# 1_MCU.net
KiCad netlist of a schematic drawn in Altium Designer
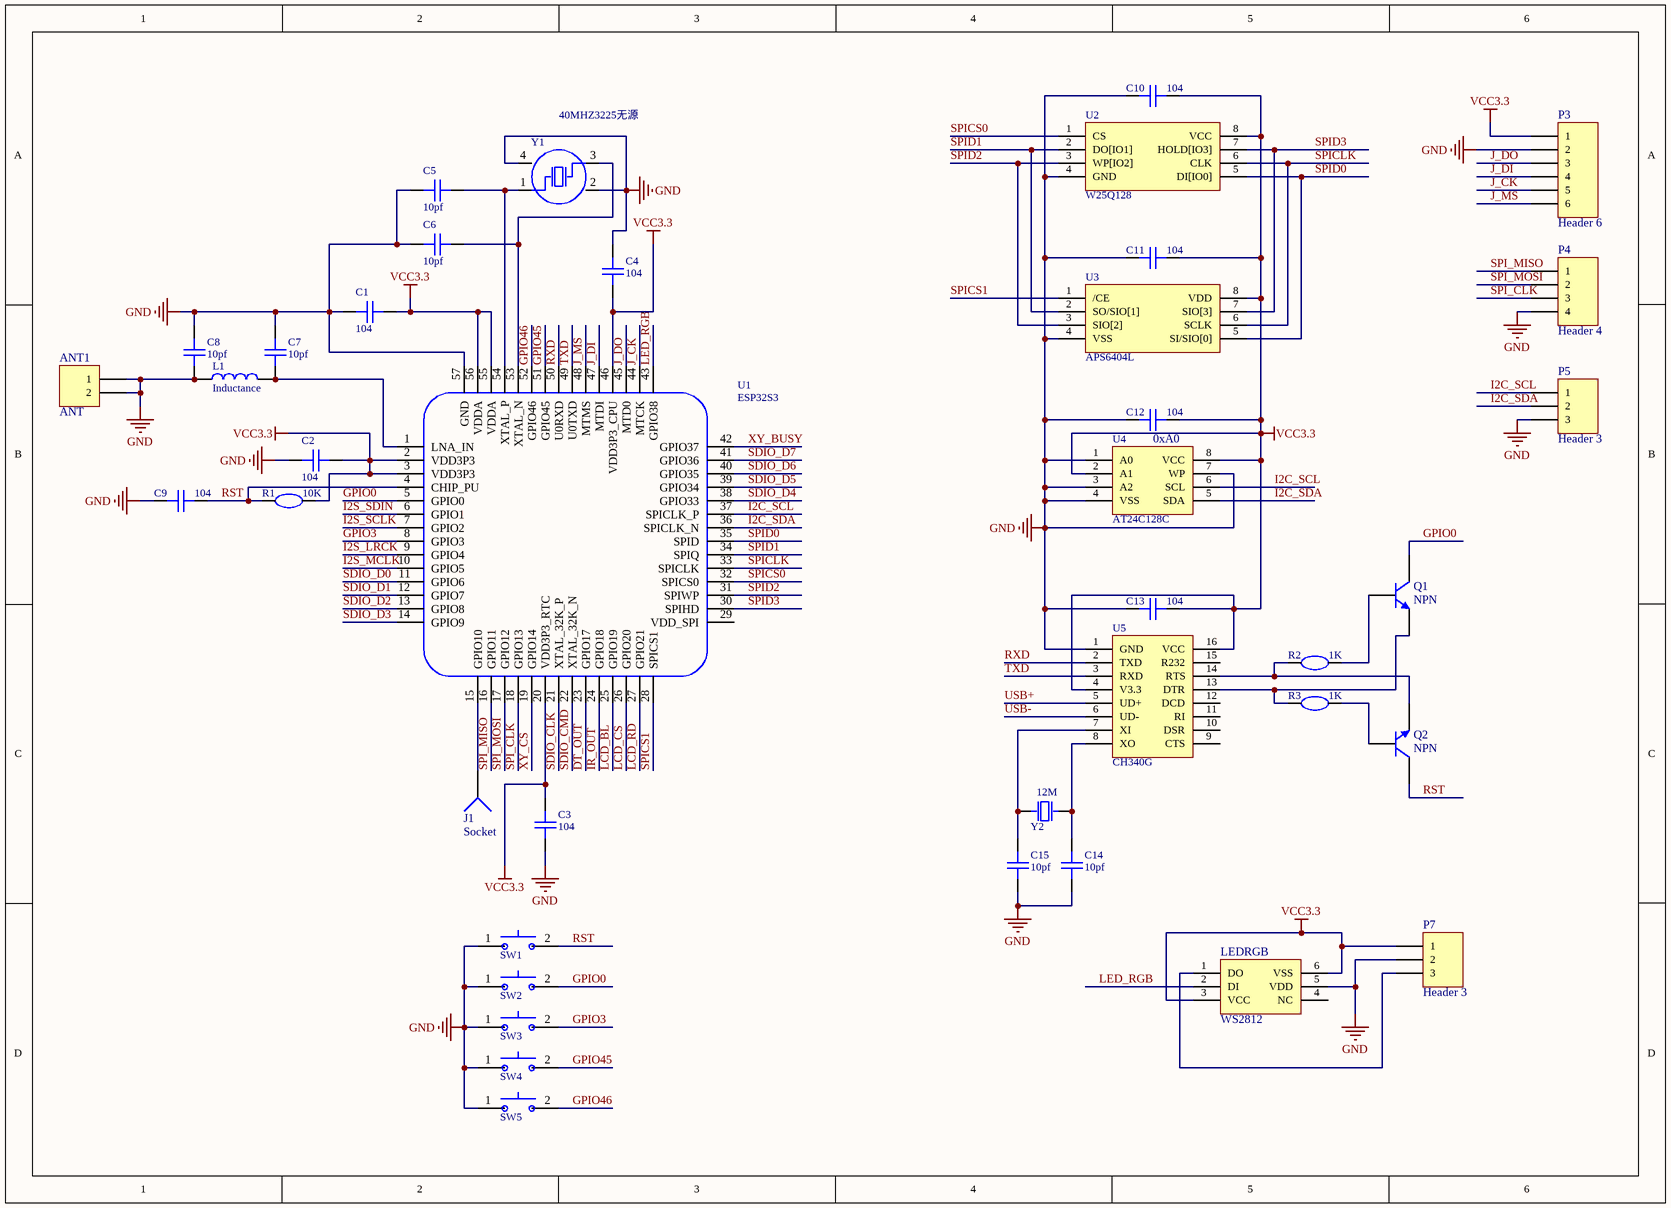
[diagram p0: 1_MCU.schdoc]

(export (version "E")
  (design (tool "Eeschema 10.0.6"))
  (components
    (comp (ref "ANT1")
      (value "ANT")
      (footprint "MINI_ANT")
      (fields (field (name "PUBLISHER") "Altium Limited"))
      (libsource (lib "Miscellaneous Connectors") (part "Header 2"))
    )
    (comp (ref "C1") (value "104") (footprint "0402R") (libsource (lib "sch") (part "CAP")))
    (comp (ref "C2") (value "104") (footprint "0402R") (libsource (lib "sch") (part "CAP")))
    (comp (ref "C3") (value "104") (footprint "0402R") (libsource (lib "sch") (part "CAP")))
    (comp (ref "C4") (value "104") (footprint "0402R") (libsource (lib "sch") (part "CAP")))
    (comp (ref "C5") (value "10pf") (footprint "0603") (libsource (lib "sch") (part "CAP")))
    (comp (ref "C6") (value "10pf") (footprint "0603") (libsource (lib "sch") (part "CAP")))
    (comp (ref "C7") (value "10pf") (footprint "0603") (libsource (lib "sch") (part "CAP")))
    (comp (ref "C8") (value "10pf") (footprint "0603") (libsource (lib "sch") (part "CAP")))
    (comp (ref "C9") (value "104") (footprint "0402R") (libsource (lib "sch") (part "CAP")))
    (comp (ref "C10") (value "104") (footprint "0402R") (libsource (lib "sch") (part "CAP")))
    (comp (ref "C11") (value "104") (footprint "0402R") (libsource (lib "sch") (part "CAP")))
    (comp (ref "C12") (value "104") (footprint "0402R") (libsource (lib "sch") (part "CAP")))
    (comp (ref "C13") (value "104") (footprint "0402R") (libsource (lib "sch") (part "CAP")))
    (comp (ref "C14") (value "10pf") (footprint "0603") (libsource (lib "sch") (part "CAP")))
    (comp (ref "C15") (value "10pf") (footprint "0603") (libsource (lib "sch") (part "CAP")))
    (comp (ref "J1")
      (value "Socket")
      (footprint "PIN1")
      (fields (field (name "PUBLISHER") "Altium Limited"))
      (libsource (lib "Miscellaneous Connectors") (part "Socket"))
    )
    (comp (ref "L1") (value "Inductance") (footprint "0603") (libsource (lib "sch") (part "Inductance")))
    (comp (ref "LEDRGB")
      (value "WS2812")
      (footprint "LED-SMD_6P-L5.0-W5.0-TL")
      (libsource (lib "sch") (part "WS2812"))
    )
    (comp (ref "P3")
      (value "Header 6")
      (footprint "HDR1X6")
      (description "Header, 6-Pin")
      (fields (field (name "PUBLISHER") "Altium Limited"))
      (libsource (lib "Miscellaneous Connectors") (part "Header 6"))
    )
    (comp (ref "P4")
      (value "Header 4")
      (footprint "HDR1X4")
      (description "Header, 4-Pin")
      (fields (field (name "PUBLISHER") "Altium Limited"))
      (libsource (lib "Miscellaneous Connectors") (part "Header 4"))
    )
    (comp (ref "P5")
      (value "Header 3")
      (footprint "HDR1X3")
      (description "Header, 3-Pin")
      (fields (field (name "PUBLISHER") "Altium Limited"))
      (libsource (lib "Miscellaneous Connectors") (part "Header 3"))
    )
    (comp (ref "P7")
      (value "Header 3")
      (footprint "HDR1X3")
      (description "Header, 3-Pin")
      (fields (field (name "PUBLISHER") "Altium Limited"))
      (libsource (lib "Miscellaneous Connectors") (part "Header 3"))
    )
    (comp (ref "Q1")
      (value "NPN")
      (footprint "SOT-23-3_L2.9-W1.3-P1.90-LS2.4-BR")
      (description "NPN Bipolar Transistor")
      (fields (field (name "PUBLISHER") "Altium Limited"))
      (libsource (lib "Miscellaneous Devices") (part "NPN"))
    )
    (comp (ref "Q2")
      (value "NPN")
      (footprint "SOT-23-3_L2.9-W1.3-P1.90-LS2.4-BR")
      (description "NPN Bipolar Transistor")
      (fields (field (name "PUBLISHER") "Altium Limited"))
      (libsource (lib "Miscellaneous Devices") (part "NPN"))
    )
    (comp (ref "R1") (value "10K") (footprint "0402R") (libsource (lib "sch") (part "RST")))
    (comp (ref "R2") (value "1K") (footprint "0402R") (libsource (lib "sch") (part "RST")))
    (comp (ref "R3") (value "1K") (footprint "0402R") (libsource (lib "sch") (part "RST")))
    (comp (ref "SW1")
      (value "无声微动开关")
      (footprint "SW-SMD_L6.0-W6.0-P6.00-LS6.6")
      (libsource (lib "sch") (part "SW"))
    )
    (comp (ref "SW2")
      (value "无声微动开关")
      (footprint "SW-SMD_L6.0-W6.0-P6.00-LS6.6")
      (libsource (lib "sch") (part "SW"))
    )
    (comp (ref "SW3")
      (value "无声微动开关")
      (footprint "SW-SMD_L6.0-W6.0-P6.00-LS6.6")
      (libsource (lib "sch") (part "SW"))
    )
    (comp (ref "SW4")
      (value "无声微动开关")
      (footprint "SW-SMD_L6.0-W6.0-P6.00-LS6.6")
      (libsource (lib "sch") (part "SW"))
    )
    (comp (ref "SW5")
      (value "无声微动开关")
      (footprint "SW-SMD_L6.0-W6.0-P6.00-LS6.6")
      (libsource (lib "sch") (part "SW"))
    )
    (comp (ref "U1") (value "ESP32S3") (footprint "ESP32-S3-QFN56") (libsource (lib "sch") (part "ESP32S3")))
    (comp (ref "U2")
      (value "W25Q128")
      (footprint "SOIC-8_L5.3-W5.3-P1.27-LS8.0-BL")
      (libsource (lib "sch") (part "W25Q128"))
    )
    (comp (ref "U3")
      (value "APS6404L")
      (footprint "SOP-8_L4.9-W3.9-P1.27-LS6.0-BL")
      (libsource (lib "sch") (part "APS6404L"))
    )
    (comp (ref "U4")
      (value "AT24C128C")
      (footprint "SOIC-8_L4.9-W3.9-P1.27-LS6.0-BL")
      (libsource (lib "sch") (part "AT24C128C"))
    )
    (comp (ref "U5") (value "CH340G") (footprint "CH340G") (libsource (lib "sch") (part "CH340G")))
    (comp (ref "Y1")
      (value "CRYSTAL1")
      (footprint "CRYSTAL-SMD_4P-L3.2-W2.5-BL")
      (fields (field (name "NAME") "40MHZ3225无源"))
      (libsource (lib "sch") (part "CRYSTAL1"))
    )
    (comp (ref "Y2")
      (value "12M")
      (footprint "HC-49US_L11.5-W4.5-P4.88")
      (libsource (lib "sch") (part "CRYSTAL"))
    )
  )
  (nets
    (net (code "1") (name "/DT_OUT") (class "Default")
      (node (ref "U1") (pin "23") (pinfunction "GPIO17_23") (pintype "passive"))
    )
    (net (code "2") (name "/GPIO0") (class "Default")
      (node (ref "Q1") (pin "1") (pinfunction "C_1") (pintype "passive"))
      (node (ref "SW2") (pin "2") (pinfunction "2_2") (pintype "passive"))
      (node (ref "U1") (pin "5") (pinfunction "GPIO0_5") (pintype "passive"))
    )
    (net (code "3") (name "/GPIO3") (class "Default")
      (node (ref "SW3") (pin "2") (pinfunction "2_2") (pintype "passive"))
      (node (ref "U1") (pin "8") (pinfunction "GPIO3_8") (pintype "passive"))
    )
    (net (code "4") (name "/GPIO45") (class "Default")
      (node (ref "SW4") (pin "2") (pinfunction "2_2") (pintype "passive"))
      (node (ref "U1") (pin "51") (pinfunction "GPIO45_51") (pintype "passive"))
    )
    (net (code "5") (name "/GPIO46") (class "Default")
      (node (ref "SW5") (pin "2") (pinfunction "2_2") (pintype "passive"))
      (node (ref "U1") (pin "52") (pinfunction "GPIO46_52") (pintype "passive"))
    )
    (net (code "6") (name "/I2C_SCL") (class "Default")
      (node (ref "P5") (pin "1") (pinfunction "1_1") (pintype "passive"))
      (node (ref "U1") (pin "37") (pinfunction "SPICLK_P_37") (pintype "passive"))
      (node (ref "U4") (pin "6") (pinfunction "SCL_6") (pintype "passive"))
    )
    (net (code "7") (name "/I2C_SDA") (class "Default")
      (node (ref "P5") (pin "2") (pinfunction "2_2") (pintype "passive"))
      (node (ref "U1") (pin "36") (pinfunction "SPICLK_N_36") (pintype "passive"))
      (node (ref "U4") (pin "5") (pinfunction "SDA_5") (pintype "passive"))
    )
    (net (code "8") (name "/I2S_LRCK") (class "Default")
      (node (ref "U1") (pin "9") (pinfunction "GPIO4_9") (pintype "passive"))
    )
    (net (code "9") (name "/I2S_MCLK") (class "Default")
      (node (ref "U1") (pin "10") (pinfunction "GPIO5_10") (pintype "passive"))
    )
    (net (code "10") (name "/I2S_SCLK") (class "Default")
      (node (ref "U1") (pin "7") (pinfunction "GPIO2_7") (pintype "passive"))
    )
    (net (code "11") (name "/I2S_SDIN") (class "Default")
      (node (ref "U1") (pin "6") (pinfunction "GPIO1_6") (pintype "passive"))
    )
    (net (code "12") (name "/IR_OUT") (class "Default")
      (node (ref "U1") (pin "24") (pinfunction "GPIO18_24") (pintype "passive"))
    )
    (net (code "13") (name "/J_CK") (class "Default")
      (node (ref "P3") (pin "5") (pinfunction "5_5") (pintype "passive"))
      (node (ref "U1") (pin "44") (pinfunction "MTCK_44") (pintype "passive"))
    )
    (net (code "14") (name "/J_DI") (class "Default")
      (node (ref "P3") (pin "4") (pinfunction "4_4") (pintype "passive"))
      (node (ref "U1") (pin "47") (pinfunction "MTDI_47") (pintype "passive"))
    )
    (net (code "15") (name "/J_DO") (class "Default")
      (node (ref "P3") (pin "3") (pinfunction "3_3") (pintype "passive"))
      (node (ref "U1") (pin "45") (pinfunction "MTD0_45") (pintype "passive"))
    )
    (net (code "16") (name "/J_MS") (class "Default")
      (node (ref "P3") (pin "6") (pinfunction "6_6") (pintype "passive"))
      (node (ref "U1") (pin "48") (pinfunction "MTMS_48") (pintype "passive"))
    )
    (net (code "17") (name "/LCD_BL") (class "Default")
      (node (ref "U1") (pin "25") (pinfunction "GPIO19_25") (pintype "passive"))
    )
    (net (code "18") (name "/LCD_CS") (class "Default")
      (node (ref "U1") (pin "26") (pinfunction "GPIO20_26") (pintype "passive"))
    )
    (net (code "19") (name "/LCD_R~{D}") (class "Default")
      (node (ref "U1") (pin "27") (pinfunction "GPIO21_27") (pintype "passive"))
    )
    (net (code "20") (name "/LED_RGB") (class "Default")
      (node (ref "LEDRGB") (pin "2") (pinfunction "DI_2") (pintype "passive"))
      (node (ref "U1") (pin "43") (pinfunction "GPIO38_43") (pintype "passive"))
    )
    (net (code "21") (name "/RST") (class "Default")
      (node (ref "C9") (pin "2") (pinfunction "2_2") (pintype "passive"))
      (node (ref "Q2") (pin "1") (pinfunction "C_1") (pintype "passive"))
      (node (ref "R1") (pin "1") (pinfunction "1_1") (pintype "passive"))
      (node (ref "SW1") (pin "2") (pinfunction "2_2") (pintype "passive"))
      (node (ref "U1") (pin "4") (pinfunction "CHIP_PU_4") (pintype "passive"))
    )
    (net (code "22") (name "/RXD") (class "Default")
      (node (ref "U1") (pin "50") (pinfunction "U0RXD_50") (pintype "passive"))
      (node (ref "U5") (pin "2") (pinfunction "TXD_2") (pintype "passive"))
    )
    (net (code "23") (name "/SDIO_CLK") (class "Default")
      (node (ref "U1") (pin "21") (pinfunction "XTAL_32K_P_21") (pintype "passive"))
    )
    (net (code "24") (name "/SDIO_CMD") (class "Default")
      (node (ref "U1") (pin "22") (pinfunction "XTAL_32K_N_22") (pintype "passive"))
    )
    (net (code "25") (name "/SDIO_D0") (class "Default")
      (node (ref "U1") (pin "11") (pinfunction "GPIO6_11") (pintype "passive"))
    )
    (net (code "26") (name "/SDIO_D1") (class "Default")
      (node (ref "U1") (pin "12") (pinfunction "GPIO7_12") (pintype "passive"))
    )
    (net (code "27") (name "/SDIO_D2") (class "Default")
      (node (ref "U1") (pin "13") (pinfunction "GPIO8_13") (pintype "passive"))
    )
    (net (code "28") (name "/SDIO_D3") (class "Default")
      (node (ref "U1") (pin "14") (pinfunction "GPIO9_14") (pintype "passive"))
    )
    (net (code "29") (name "/SDIO_D4") (class "Default")
      (node (ref "U1") (pin "38") (pinfunction "GPIO33_38") (pintype "passive"))
    )
    (net (code "30") (name "/SDIO_D5") (class "Default")
      (node (ref "U1") (pin "39") (pinfunction "GPIO34_39") (pintype "passive"))
    )
    (net (code "31") (name "/SDIO_D6") (class "Default")
      (node (ref "U1") (pin "40") (pinfunction "GPIO35_40") (pintype "passive"))
    )
    (net (code "32") (name "/SDIO_D7") (class "Default")
      (node (ref "U1") (pin "41") (pinfunction "GPIO36_41") (pintype "passive"))
    )
    (net (code "33") (name "/SPICLK") (class "Default")
      (node (ref "U1") (pin "33") (pinfunction "SPICLK_33") (pintype "passive"))
      (node (ref "U2") (pin "6") (pinfunction "CLK_6") (pintype "passive"))
      (node (ref "U3") (pin "6") (pinfunction "SCLK_6") (pintype "passive"))
    )
    (net (code "34") (name "/SPICS0") (class "Default")
      (node (ref "U1") (pin "32") (pinfunction "SPICS0_32") (pintype "passive"))
      (node (ref "U2") (pin "1") (pinfunction "CS_1") (pintype "passive"))
    )
    (net (code "35") (name "/SPICS1") (class "Default")
      (node (ref "U1") (pin "28") (pinfunction "SPICS1_28") (pintype "passive"))
      (node (ref "U3") (pin "1") (pinfunction "/CE_1") (pintype "passive"))
    )
    (net (code "36") (name "/SPID0") (class "Default")
      (node (ref "U1") (pin "35") (pinfunction "SPID_35") (pintype "passive"))
      (node (ref "U2") (pin "5") (pinfunction "DI[IO0]_5") (pintype "passive"))
      (node (ref "U3") (pin "5") (pinfunction "SI/SIO[0]_5") (pintype "passive"))
    )
    (net (code "37") (name "/SPID1") (class "Default")
      (node (ref "U1") (pin "34") (pinfunction "SPIQ_34") (pintype "passive"))
      (node (ref "U2") (pin "2") (pinfunction "DO[IO1]_2") (pintype "passive"))
      (node (ref "U3") (pin "2") (pinfunction "SO/SIO[1]_2") (pintype "passive"))
    )
    (net (code "38") (name "/SPID2") (class "Default")
      (node (ref "U1") (pin "31") (pinfunction "SPIWP_31") (pintype "passive"))
      (node (ref "U2") (pin "3") (pinfunction "WP[IO2]_3") (pintype "passive"))
      (node (ref "U3") (pin "3") (pinfunction "SIO[2]_3") (pintype "passive"))
    )
    (net (code "39") (name "/SPID3") (class "Default")
      (node (ref "U1") (pin "30") (pinfunction "SPIHD_30") (pintype "passive"))
      (node (ref "U2") (pin "7") (pinfunction "HOLD[IO3]_7") (pintype "passive"))
      (node (ref "U3") (pin "7") (pinfunction "SIO[3]_7") (pintype "passive"))
    )
    (net (code "40") (name "/SPI_CLK") (class "Default")
      (node (ref "P4") (pin "3") (pinfunction "3_3") (pintype "passive"))
      (node (ref "U1") (pin "18") (pinfunction "GPIO13_18") (pintype "passive"))
    )
    (net (code "41") (name "/SPI_MISO") (class "Default")
      (node (ref "P4") (pin "1") (pinfunction "1_1") (pintype "passive"))
      (node (ref "U1") (pin "16") (pinfunction "GPIO11_16") (pintype "passive"))
    )
    (net (code "42") (name "/SPI_MOSI") (class "Default")
      (node (ref "P4") (pin "2") (pinfunction "2_2") (pintype "passive"))
      (node (ref "U1") (pin "17") (pinfunction "GPIO12_17") (pintype "passive"))
    )
    (net (code "43") (name "/TXD") (class "Default")
      (node (ref "U1") (pin "49") (pinfunction "U0TXD_49") (pintype "passive"))
      (node (ref "U5") (pin "3") (pinfunction "RXD_3") (pintype "passive"))
    )
    (net (code "44") (name "/USB+") (class "Default")
      (node (ref "U5") (pin "5") (pinfunction "UD+_5") (pintype "passive"))
    )
    (net (code "45") (name "/USB-") (class "Default")
      (node (ref "U5") (pin "6") (pinfunction "UD-_6") (pintype "passive"))
    )
    (net (code "46") (name "/XY_BUSY") (class "Default")
      (node (ref "U1") (pin "42") (pinfunction "GPIO37_42") (pintype "passive"))
    )
    (net (code "47") (name "/XY_CS") (class "Default")
      (node (ref "U1") (pin "19") (pinfunction "GPIO14_19") (pintype "passive"))
    )
    (net (code "48") (name "GND") (class "Default")
      (node (ref "ANT1") (pin "1") (pinfunction "1_1") (pintype "passive"))
      (node (ref "ANT1") (pin "2") (pinfunction "2_2") (pintype "passive"))
      (node (ref "C1") (pin "1") (pinfunction "1_1") (pintype "passive"))
      (node (ref "C10") (pin "1") (pinfunction "1_1") (pintype "passive"))
      (node (ref "C11") (pin "1") (pinfunction "1_1") (pintype "passive"))
      (node (ref "C12") (pin "1") (pinfunction "1_1") (pintype "passive"))
      (node (ref "C13") (pin "1") (pinfunction "1_1") (pintype "passive"))
      (node (ref "C14") (pin "1") (pinfunction "1_1") (pintype "passive"))
      (node (ref "C15") (pin "1") (pinfunction "1_1") (pintype "passive"))
      (node (ref "C2") (pin "1") (pinfunction "1_1") (pintype "passive"))
      (node (ref "C3") (pin "1") (pinfunction "1_1") (pintype "passive"))
      (node (ref "C4") (pin "2") (pinfunction "2_2") (pintype "passive"))
      (node (ref "C5") (pin "1") (pinfunction "1_1") (pintype "passive"))
      (node (ref "C6") (pin "1") (pinfunction "1_1") (pintype "passive"))
      (node (ref "C7") (pin "2") (pinfunction "2_2") (pintype "passive"))
      (node (ref "C8") (pin "1") (pinfunction "1_1") (pintype "passive"))
      (node (ref "C8") (pin "2") (pinfunction "2_2") (pintype "passive"))
      (node (ref "C9") (pin "1") (pinfunction "1_1") (pintype "passive"))
      (node (ref "L1") (pin "1") (pinfunction "1_1") (pintype "passive"))
      (node (ref "LEDRGB") (pin "5") (pinfunction "VDD_5") (pintype "passive"))
      (node (ref "P3") (pin "2") (pinfunction "2_2") (pintype "passive"))
      (node (ref "P4") (pin "4") (pinfunction "4_4") (pintype "passive"))
      (node (ref "P5") (pin "3") (pinfunction "3_3") (pintype "passive"))
      (node (ref "P7") (pin "2") (pinfunction "2_2") (pintype "passive"))
      (node (ref "SW1") (pin "1") (pinfunction "1_1") (pintype "passive"))
      (node (ref "SW2") (pin "1") (pinfunction "1_1") (pintype "passive"))
      (node (ref "SW3") (pin "1") (pinfunction "1_1") (pintype "passive"))
      (node (ref "SW4") (pin "1") (pinfunction "1_1") (pintype "passive"))
      (node (ref "SW5") (pin "1") (pinfunction "1_1") (pintype "passive"))
      (node (ref "U1") (pin "57") (pinfunction "GND_57") (pintype "passive"))
      (node (ref "U2") (pin "4") (pinfunction "GND_4") (pintype "passive"))
      (node (ref "U3") (pin "4") (pinfunction "VSS_4") (pintype "passive"))
      (node (ref "U4") (pin "1") (pinfunction "A0_1") (pintype "passive"))
      (node (ref "U4") (pin "3") (pinfunction "A2_3") (pintype "passive"))
      (node (ref "U4") (pin "4") (pinfunction "VSS_4") (pintype "passive"))
      (node (ref "U4") (pin "7") (pinfunction "WP_7") (pintype "passive"))
      (node (ref "U5") (pin "1") (pinfunction "GND_1") (pintype "passive"))
      (node (ref "Y1") (pin "2") (pinfunction "GND_2") (pintype "passive"))
      (node (ref "Y1") (pin "4") (pinfunction "GND_4") (pintype "passive"))
    )
    (net (code "49") (name "Net-(LEDRGB-DO)") (class "Default")
      (node (ref "LEDRGB") (pin "1") (pinfunction "DO_1") (pintype "passive"))
      (node (ref "P7") (pin "3") (pinfunction "3_3") (pintype "passive"))
    )
    (net (code "50") (name "Net-(Q1-B)") (class "Default")
      (node (ref "Q1") (pin "2") (pinfunction "B_2") (pintype "passive"))
      (node (ref "R2") (pin "2") (pinfunction "2_2") (pintype "passive"))
    )
    (net (code "51") (name "Net-(Q1-E)") (class "Default")
      (node (ref "Q1") (pin "3") (pinfunction "E_3") (pintype "passive"))
      (node (ref "R3") (pin "1") (pinfunction "1_1") (pintype "passive"))
      (node (ref "U5") (pin "13") (pinfunction "DTR_13") (pintype "passive"))
    )
    (net (code "52") (name "Net-(Q2-B)") (class "Default")
      (node (ref "Q2") (pin "2") (pinfunction "B_2") (pintype "passive"))
      (node (ref "R3") (pin "2") (pinfunction "2_2") (pintype "passive"))
    )
    (net (code "53") (name "Net-(Q2-E)") (class "Default")
      (node (ref "Q2") (pin "3") (pinfunction "E_3") (pintype "passive"))
      (node (ref "R2") (pin "1") (pinfunction "1_1") (pintype "passive"))
      (node (ref "U5") (pin "14") (pinfunction "RTS_14") (pintype "passive"))
    )
    (net (code "54") (name "Net-(U1-GPIO10)") (class "Default")
      (node (ref "J1") (pin "1") (pinfunction "1_1") (pintype "passive"))
      (node (ref "U1") (pin "15") (pinfunction "GPIO10_15") (pintype "passive"))
    )
    (net (code "55") (name "Net-(U1-LNA_IN)") (class "Default")
      (node (ref "C7") (pin "1") (pinfunction "1_1") (pintype "passive"))
      (node (ref "L1") (pin "2") (pinfunction "2_2") (pintype "passive"))
      (node (ref "U1") (pin "1") (pinfunction "LNA_IN_1") (pintype "passive"))
    )
    (net (code "56") (name "Net-(U1-XTAL_N)") (class "Default")
      (node (ref "C6") (pin "2") (pinfunction "2_2") (pintype "passive"))
      (node (ref "U1") (pin "53") (pinfunction "XTAL_N_53") (pintype "passive"))
      (node (ref "Y1") (pin "3") (pinfunction "OSC2_3") (pintype "passive"))
    )
    (net (code "57") (name "Net-(U1-XTAL_P)") (class "Default")
      (node (ref "C5") (pin "2") (pinfunction "2_2") (pintype "passive"))
      (node (ref "U1") (pin "54") (pinfunction "XTAL_P_54") (pintype "passive"))
      (node (ref "Y1") (pin "1") (pinfunction "OSC1_1") (pintype "passive"))
    )
    (net (code "58") (name "Net-(U5-XI)") (class "Default")
      (node (ref "C15") (pin "2") (pinfunction "2_2") (pintype "passive"))
      (node (ref "U5") (pin "7") (pinfunction "XI_7") (pintype "passive"))
      (node (ref "Y2") (pin "1") (pinfunction "OSC1_1") (pintype "passive"))
    )
    (net (code "59") (name "Net-(U5-XO)") (class "Default")
      (node (ref "C14") (pin "2") (pinfunction "2_2") (pintype "passive"))
      (node (ref "U5") (pin "8") (pinfunction "XO_8") (pintype "passive"))
      (node (ref "Y2") (pin "2") (pinfunction "OSC2_2") (pintype "passive"))
    )
    (net (code "60") (name "VCC3.3") (class "Default")
      (node (ref "C1") (pin "2") (pinfunction "2_2") (pintype "passive"))
      (node (ref "C10") (pin "2") (pinfunction "2_2") (pintype "passive"))
      (node (ref "C11") (pin "2") (pinfunction "2_2") (pintype "passive"))
      (node (ref "C12") (pin "2") (pinfunction "2_2") (pintype "passive"))
      (node (ref "C13") (pin "2") (pinfunction "2_2") (pintype "passive"))
      (node (ref "C2") (pin "2") (pinfunction "2_2") (pintype "passive"))
      (node (ref "C3") (pin "2") (pinfunction "2_2") (pintype "passive"))
      (node (ref "C4") (pin "1") (pinfunction "1_1") (pintype "passive"))
      (node (ref "LEDRGB") (pin "3") (pinfunction "VCC_3") (pintype "passive"))
      (node (ref "LEDRGB") (pin "6") (pinfunction "VSS_6") (pintype "passive"))
      (node (ref "P3") (pin "1") (pinfunction "1_1") (pintype "passive"))
      (node (ref "P7") (pin "1") (pinfunction "1_1") (pintype "passive"))
      (node (ref "R1") (pin "2") (pinfunction "2_2") (pintype "passive"))
      (node (ref "U1") (pin "2") (pinfunction "VDD3P3_2") (pintype "passive"))
      (node (ref "U1") (pin "20") (pinfunction "VDD3P3_RTC_20") (pintype "passive"))
      (node (ref "U1") (pin "3") (pinfunction "VDD3P3_3") (pintype "passive"))
      (node (ref "U1") (pin "46") (pinfunction "VDD3P3_CPU_46") (pintype "passive"))
      (node (ref "U1") (pin "55") (pinfunction "VDDA_55") (pintype "passive"))
      (node (ref "U1") (pin "56") (pinfunction "VDDA_56") (pintype "passive"))
      (node (ref "U2") (pin "8") (pinfunction "VCC_8") (pintype "passive"))
      (node (ref "U3") (pin "8") (pinfunction "VDD_8") (pintype "passive"))
      (node (ref "U4") (pin "2") (pinfunction "A1_2") (pintype "passive"))
      (node (ref "U4") (pin "8") (pinfunction "VCC_8") (pintype "passive"))
      (node (ref "U5") (pin "16") (pinfunction "VCC_16") (pintype "passive"))
      (node (ref "U5") (pin "4") (pinfunction "V3.3_4") (pintype "passive"))
    )
    (net (code "61") (name "unconnected-(LEDRGB-NC-Pad4)") (class "Default")
      (node (ref "LEDRGB") (pin "4") (pinfunction "NC_4") (pintype "passive"))
    )
    (net (code "62") (name "unconnected-(U1-VDD_SPI-Pad29)") (class "Default")
      (node (ref "U1") (pin "29") (pinfunction "VDD_SPI_29") (pintype "passive"))
    )
    (net (code "63") (name "unconnected-(U5-CTS-Pad9)") (class "Default")
      (node (ref "U5") (pin "9") (pinfunction "CTS_9") (pintype "passive"))
    )
    (net (code "64") (name "unconnected-(U5-DCD-Pad12)") (class "Default")
      (node (ref "U5") (pin "12") (pinfunction "DCD_12") (pintype "passive"))
    )
    (net (code "65") (name "unconnected-(U5-DSR-Pad10)") (class "Default")
      (node (ref "U5") (pin "10") (pinfunction "DSR_10") (pintype "passive"))
    )
    (net (code "66") (name "unconnected-(U5-R232-Pad15)") (class "Default")
      (node (ref "U5") (pin "15") (pinfunction "R232_15") (pintype "passive"))
    )
    (net (code "67") (name "unconnected-(U5-RI-Pad11)") (class "Default")
      (node (ref "U5") (pin "11") (pinfunction "RI_11") (pintype "passive"))
    )
  )
)
